# board.net
KiCad netlist of a schematic drawn in EAGLE
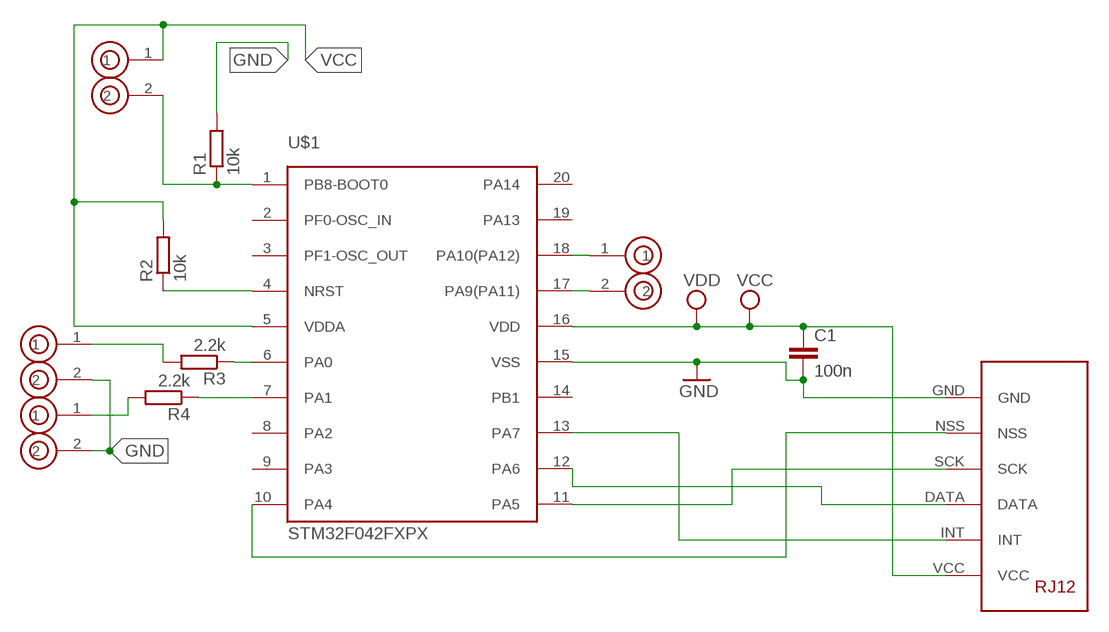
[diagram p0: schematic, sheet 1]

(export (version "E")
  (design (tool "Eeschema 10.0.6"))
  (components
    (comp (ref "C1")
      (value "100n")
      (footprint "eagle-import:C1206K")
      (libsource (lib "eagle-import") (part "C-EUC1206K"))
    )
    (comp (ref "R1")
      (value "10k")
      (footprint "eagle-import:R0805")
      (libsource (lib "eagle-import") (part "R-EU_R0805"))
    )
    (comp (ref "R2")
      (value "10k")
      (footprint "eagle-import:R0805")
      (libsource (lib "eagle-import") (part "R-EU_R0805"))
    )
    (comp (ref "R3")
      (value "2.2k")
      (footprint "eagle-import:R0805")
      (libsource (lib "eagle-import") (part "R-EU_R0805"))
    )
    (comp (ref "R4")
      (value "2.2k")
      (footprint "eagle-import:R0805")
      (libsource (lib "eagle-import") (part "R-EU_R0805"))
    )
    (comp (ref "U$1")
      (value "STM32F042FXPX")
      (footprint "eagle-import:TSSOP20")
      (libsource (lib "eagle-import") (part "STM32F042FXPX"))
    )
    (comp (ref "U$2")
      (value "RJ12SMD")
      (footprint "eagle-import:RJ12_SMD")
      (libsource (lib "eagle-import") (part "RJ12SMD"))
    )
    (comp (ref "U$3")
      (value "GOLDPIN_2")
      (footprint "eagle-import:GOLDPIN_2_SMD")
      (libsource (lib "eagle-import") (part "GOLDPIN_2"))
    )
    (comp (ref "U$4")
      (value "GOLDPIN_2")
      (footprint "eagle-import:GOLDPIN_2_SMD")
      (libsource (lib "eagle-import") (part "GOLDPIN_2"))
    )
    (comp (ref "U$5")
      (value "GOLDPIN_2")
      (footprint "eagle-import:GOLDPIN_2_SMD")
      (libsource (lib "eagle-import") (part "GOLDPIN_2"))
    )
    (comp (ref "U$6")
      (value "GOLDPIN_2")
      (footprint "eagle-import:GOLDPIN_2_SMD")
      (libsource (lib "eagle-import") (part "GOLDPIN_2"))
    )
  )
  (nets
    (net (code "1") (name "GND") (class "Default")
      (node (ref "C1") (pin "2") (pinfunction "2_2") (pintype "passive"))
      (node (ref "R1") (pin "2") (pinfunction "2_2") (pintype "passive"))
      (node (ref "U$1") (pin "15") (pinfunction "VSS_15") (pintype "bidirectional"))
      (node (ref "U$2") (pin "GND") (pinfunction "GND_GND") (pintype "bidirectional"))
      (node (ref "U$5") (pin "2") (pinfunction "2_2") (pintype "bidirectional"))
      (node (ref "U$6") (pin "2") (pinfunction "2_2") (pintype "bidirectional"))
    )
    (net (code "2") (name "Net-(R3-Pad2)") (class "Default")
      (node (ref "R3") (pin "2") (pinfunction "2_2") (pintype "passive"))
      (node (ref "U$5") (pin "1") (pinfunction "1_1") (pintype "bidirectional"))
    )
    (net (code "3") (name "Net-(R4-Pad2)") (class "Default")
      (node (ref "R4") (pin "2") (pinfunction "2_2") (pintype "passive"))
      (node (ref "U$6") (pin "1") (pinfunction "1_1") (pintype "bidirectional"))
    )
    (net (code "4") (name "Net-(U$1-NRST)") (class "Default")
      (node (ref "R2") (pin "1") (pinfunction "1_1") (pintype "passive"))
      (node (ref "U$1") (pin "4") (pinfunction "NRST_4") (pintype "bidirectional"))
    )
    (net (code "5") (name "Net-(U$1-PA0)") (class "Default")
      (node (ref "R3") (pin "1") (pinfunction "1_1") (pintype "passive"))
      (node (ref "U$1") (pin "6") (pinfunction "PA0_6") (pintype "bidirectional"))
    )
    (net (code "6") (name "Net-(U$1-PA1)") (class "Default")
      (node (ref "R4") (pin "1") (pinfunction "1_1") (pintype "passive"))
      (node (ref "U$1") (pin "7") (pinfunction "PA1_7") (pintype "bidirectional"))
    )
    (net (code "7") (name "Net-(U$1-PA4)") (class "Default")
      (node (ref "U$1") (pin "10") (pinfunction "PA4_10") (pintype "bidirectional"))
      (node (ref "U$2") (pin "NSS") (pinfunction "NSS_NSS") (pintype "bidirectional"))
    )
    (net (code "8") (name "Net-(U$1-PA5)") (class "Default")
      (node (ref "U$1") (pin "11") (pinfunction "PA5_11") (pintype "bidirectional"))
      (node (ref "U$2") (pin "SCK") (pinfunction "SCK_SCK") (pintype "bidirectional"))
    )
    (net (code "9") (name "Net-(U$1-PA6)") (class "Default")
      (node (ref "U$1") (pin "12") (pinfunction "PA6_12") (pintype "bidirectional"))
      (node (ref "U$2") (pin "DATA") (pinfunction "DATA_DATA") (pintype "bidirectional"))
    )
    (net (code "10") (name "Net-(U$1-PA7)") (class "Default")
      (node (ref "U$1") (pin "13") (pinfunction "PA7_13") (pintype "bidirectional"))
      (node (ref "U$2") (pin "INT") (pinfunction "INT_INT") (pintype "bidirectional"))
    )
    (net (code "11") (name "Net-(U$1-PA9(PA11))") (class "Default")
      (node (ref "U$1") (pin "17") (pinfunction "PA9(PA11)_17") (pintype "bidirectional"))
      (node (ref "U$3") (pin "2") (pinfunction "2_2") (pintype "bidirectional"))
    )
    (net (code "12") (name "Net-(U$1-PA10(PA12))") (class "Default")
      (node (ref "U$1") (pin "18") (pinfunction "PA10(PA12)_18") (pintype "bidirectional"))
      (node (ref "U$3") (pin "1") (pinfunction "1_1") (pintype "bidirectional"))
    )
    (net (code "13") (name "Net-(U$1-PB8-BOOT0)") (class "Default")
      (node (ref "R1") (pin "1") (pinfunction "1_1") (pintype "passive"))
      (node (ref "U$1") (pin "1") (pinfunction "PB8-BOOT0_1") (pintype "bidirectional"))
      (node (ref "U$4") (pin "2") (pinfunction "2_2") (pintype "bidirectional"))
    )
    (net (code "14") (name "VCC") (class "Default")
      (node (ref "C1") (pin "1") (pinfunction "1_1") (pintype "passive"))
      (node (ref "R2") (pin "2") (pinfunction "2_2") (pintype "passive"))
      (node (ref "U$1") (pin "16") (pinfunction "VDD_16") (pintype "bidirectional"))
      (node (ref "U$1") (pin "5") (pinfunction "VDDA_5") (pintype "bidirectional"))
      (node (ref "U$2") (pin "VCC") (pinfunction "VCC_VCC") (pintype "bidirectional"))
      (node (ref "U$4") (pin "1") (pinfunction "1_1") (pintype "bidirectional"))
    )
    (net (code "15") (name "unconnected-(U$1-PA2-Pad8)") (class "Default")
      (node (ref "U$1") (pin "8") (pinfunction "PA2_8") (pintype "bidirectional"))
    )
    (net (code "16") (name "unconnected-(U$1-PA3-Pad9)") (class "Default")
      (node (ref "U$1") (pin "9") (pinfunction "PA3_9") (pintype "bidirectional"))
    )
    (net (code "17") (name "unconnected-(U$1-PA13-Pad19)") (class "Default")
      (node (ref "U$1") (pin "19") (pinfunction "PA13_19") (pintype "bidirectional"))
    )
    (net (code "18") (name "unconnected-(U$1-PA14-Pad20)") (class "Default")
      (node (ref "U$1") (pin "20") (pinfunction "PA14_20") (pintype "bidirectional"))
    )
    (net (code "19") (name "unconnected-(U$1-PB1-Pad14)") (class "Default")
      (node (ref "U$1") (pin "14") (pinfunction "PB1_14") (pintype "bidirectional"))
    )
    (net (code "20") (name "unconnected-(U$1-PF0-OSC_IN-Pad2)") (class "Default")
      (node (ref "U$1") (pin "2") (pinfunction "PF0-OSC_IN_2") (pintype "bidirectional"))
    )
    (net (code "21") (name "unconnected-(U$1-PF1-OSC_OUT-Pad3)") (class "Default")
      (node (ref "U$1") (pin "3") (pinfunction "PF1-OSC_OUT_3") (pintype "bidirectional"))
    )
  )
)
